# 4_Expansion.net
KiCad netlist of a schematic drawn in Altium Designer
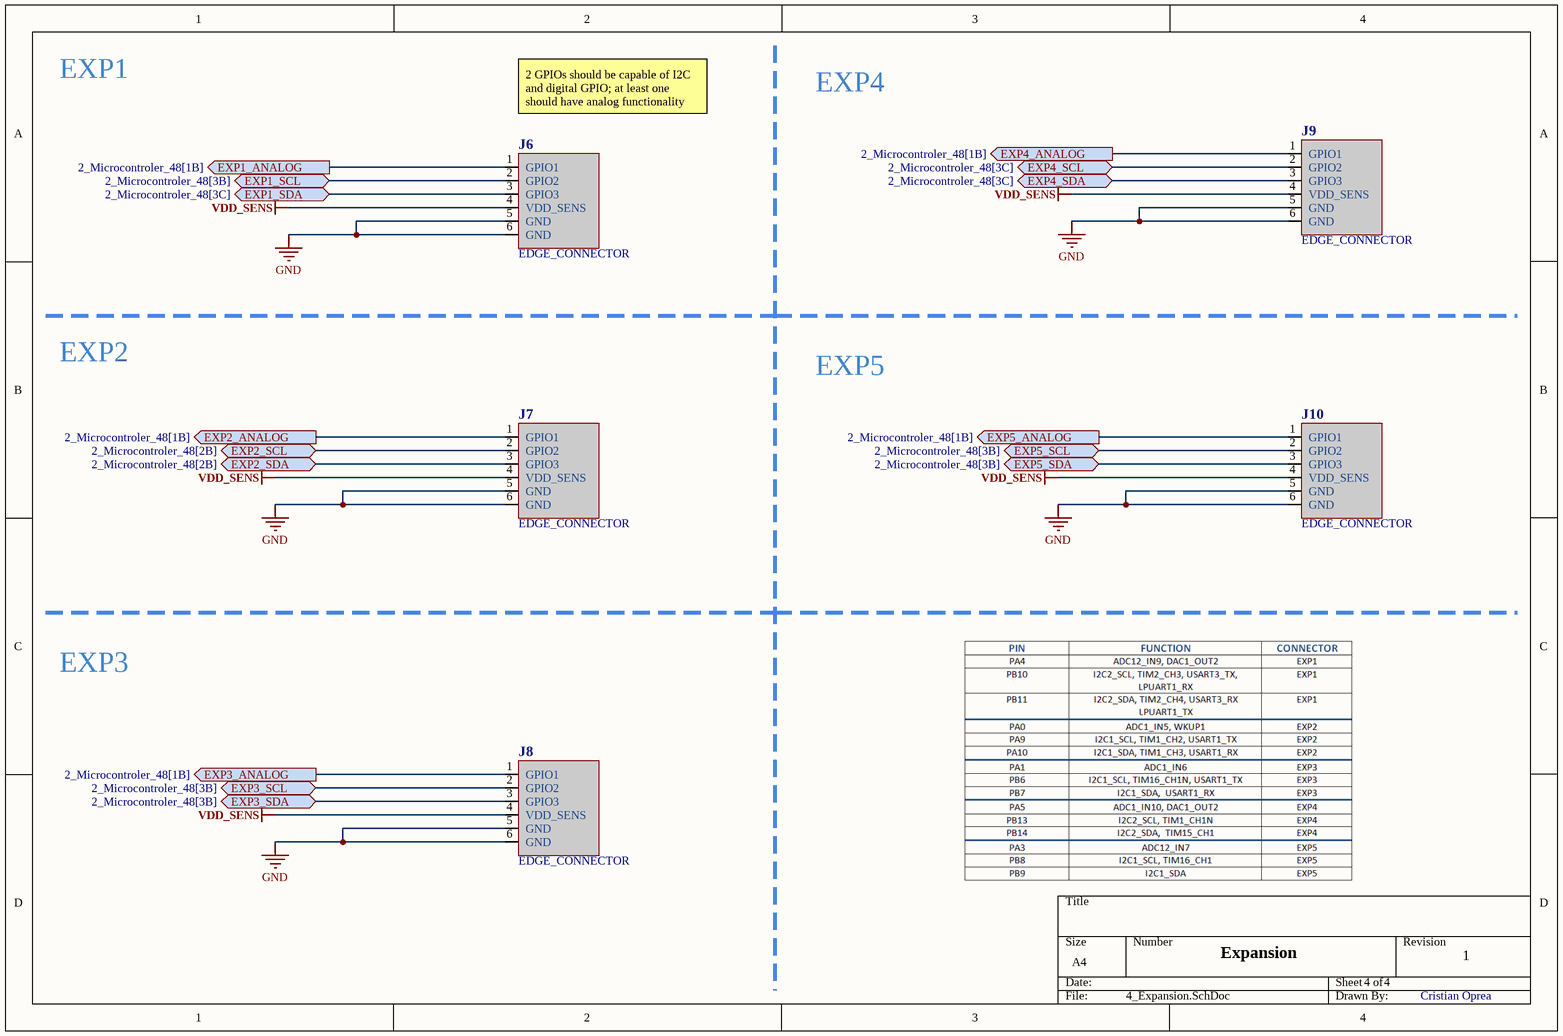
[diagram p0: 4_Expansion.SchDoc]

(export (version "E")
  (design (tool "Eeschema 10.0.6"))
  (components
    (comp (ref "J6")
      (value "EDGE_CONNECTOR")
      (footprint "2.54mm_edge_connector")
      (description "Connector for sensor modules")
      (libsource (lib "Schlib_H2") (part "edge_connector"))
    )
    (comp (ref "J7")
      (value "EDGE_CONNECTOR")
      (footprint "2.54mm_edge_connector")
      (description "Connector for sensor modules")
      (libsource (lib "Schlib_H2") (part "edge_connector"))
    )
    (comp (ref "J8")
      (value "EDGE_CONNECTOR")
      (footprint "2.54mm_edge_connector")
      (description "Connector for sensor modules")
      (libsource (lib "Schlib_H2") (part "edge_connector"))
    )
    (comp (ref "J9")
      (value "EDGE_CONNECTOR")
      (footprint "2.54mm_edge_connector")
      (description "Connector for sensor modules")
      (libsource (lib "Schlib_H2") (part "edge_connector"))
    )
    (comp (ref "J10")
      (value "EDGE_CONNECTOR")
      (footprint "2.54mm_edge_connector")
      (description "Connector for sensor modules")
      (libsource (lib "Schlib_H2") (part "edge_connector"))
    )
  )
  (nets
    (net (code "1") (name "/EXP1_ANALOG") (class "Default")
      (node (ref "J6") (pin "1") (pinfunction "GPIO1_1") (pintype "passive"))
    )
    (net (code "2") (name "/EXP1_SCL") (class "Default")
      (node (ref "J6") (pin "2") (pinfunction "GPIO2_2") (pintype "passive"))
    )
    (net (code "3") (name "/EXP1_SDA") (class "Default")
      (node (ref "J6") (pin "3") (pinfunction "GPIO3_3") (pintype "passive"))
    )
    (net (code "4") (name "/EXP2_ANALOG") (class "Default")
      (node (ref "J7") (pin "1") (pinfunction "GPIO1_1") (pintype "passive"))
    )
    (net (code "5") (name "/EXP2_SCL") (class "Default")
      (node (ref "J7") (pin "2") (pinfunction "GPIO2_2") (pintype "passive"))
    )
    (net (code "6") (name "/EXP2_SDA") (class "Default")
      (node (ref "J7") (pin "3") (pinfunction "GPIO3_3") (pintype "passive"))
    )
    (net (code "7") (name "/EXP3_ANALOG") (class "Default")
      (node (ref "J8") (pin "1") (pinfunction "GPIO1_1") (pintype "passive"))
    )
    (net (code "8") (name "/EXP3_SCL") (class "Default")
      (node (ref "J8") (pin "2") (pinfunction "GPIO2_2") (pintype "passive"))
    )
    (net (code "9") (name "/EXP3_SDA") (class "Default")
      (node (ref "J8") (pin "3") (pinfunction "GPIO3_3") (pintype "passive"))
    )
    (net (code "10") (name "/EXP4_ANALOG") (class "Default")
      (node (ref "J9") (pin "1") (pinfunction "GPIO1_1") (pintype "passive"))
    )
    (net (code "11") (name "/EXP4_SCL") (class "Default")
      (node (ref "J9") (pin "2") (pinfunction "GPIO2_2") (pintype "passive"))
    )
    (net (code "12") (name "/EXP4_SDA") (class "Default")
      (node (ref "J9") (pin "3") (pinfunction "GPIO3_3") (pintype "passive"))
    )
    (net (code "13") (name "/EXP5_ANALOG") (class "Default")
      (node (ref "J10") (pin "1") (pinfunction "GPIO1_1") (pintype "passive"))
    )
    (net (code "14") (name "/EXP5_SCL") (class "Default")
      (node (ref "J10") (pin "2") (pinfunction "GPIO2_2") (pintype "passive"))
    )
    (net (code "15") (name "/EXP5_SDA") (class "Default")
      (node (ref "J10") (pin "3") (pinfunction "GPIO3_3") (pintype "passive"))
    )
    (net (code "16") (name "GND") (class "Default")
      (node (ref "J10") (pin "5") (pinfunction "GND_5") (pintype "passive"))
      (node (ref "J10") (pin "6") (pinfunction "GND_6") (pintype "passive"))
      (node (ref "J6") (pin "5") (pinfunction "GND_5") (pintype "passive"))
      (node (ref "J6") (pin "6") (pinfunction "GND_6") (pintype "passive"))
      (node (ref "J7") (pin "5") (pinfunction "GND_5") (pintype "passive"))
      (node (ref "J7") (pin "6") (pinfunction "GND_6") (pintype "passive"))
      (node (ref "J8") (pin "5") (pinfunction "GND_5") (pintype "passive"))
      (node (ref "J8") (pin "6") (pinfunction "GND_6") (pintype "passive"))
      (node (ref "J9") (pin "5") (pinfunction "GND_5") (pintype "passive"))
      (node (ref "J9") (pin "6") (pinfunction "GND_6") (pintype "passive"))
    )
    (net (code "17") (name "VDD_SENS") (class "Default")
      (node (ref "J10") (pin "4") (pinfunction "VDD_SENS_4") (pintype "passive"))
      (node (ref "J6") (pin "4") (pinfunction "VDD_SENS_4") (pintype "passive"))
      (node (ref "J7") (pin "4") (pinfunction "VDD_SENS_4") (pintype "passive"))
      (node (ref "J8") (pin "4") (pinfunction "VDD_SENS_4") (pintype "passive"))
      (node (ref "J9") (pin "4") (pinfunction "VDD_SENS_4") (pintype "passive"))
    )
  )
)
